# TMP.net
KiCad netlist of a schematic drawn in EAGLE
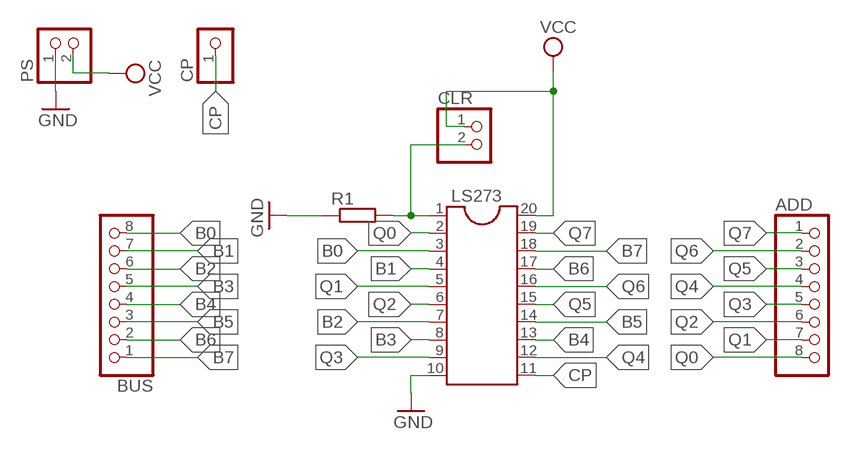
[diagram p0: schematic, sheet 1]

(export (version "E")
  (design (tool "Eeschema 10.0.6"))
  (components
    (comp (ref "ADD")
      (value "PINHD-1X8")
      (footprint "eagle-import:1X08")
      (libsource (lib "eagle-import") (part "PINHD-1X8"))
    )
    (comp (ref "BUS")
      (value "PINHD-1X8")
      (footprint "eagle-import:1X08")
      (libsource (lib "eagle-import") (part "PINHD-1X8"))
    )
    (comp (ref "CLR")
      (value "PINHD-1X2")
      (footprint "eagle-import:1X02")
      (libsource (lib "eagle-import") (part "PINHD-1X2"))
    )
    (comp (ref "CP")
      (value "PINHD-1X1")
      (footprint "eagle-import:1X01")
      (libsource (lib "eagle-import") (part "PINHD-1X1"))
    )
    (comp (ref "LS273")
      (value "DIL20S")
      (footprint "eagle-import:SOCKET-20")
      (libsource (lib "eagle-import") (part "DIL20S"))
    )
    (comp (ref "PS")
      (value "PINHD-1X2")
      (footprint "eagle-import:1X02")
      (libsource (lib "eagle-import") (part "PINHD-1X2"))
    )
    (comp (ref "R1")
      (value "R-EU_0204/7")
      (footprint "eagle-import:0204_7")
      (libsource (lib "eagle-import") (part "R-EU_0204/7"))
    )
  )
  (nets
    (net (code "1") (name "B0") (class "Default")
      (node (ref "BUS") (pin "8") (pinfunction "8_8") (pintype "passive"))
      (node (ref "LS273") (pin "3") (pinfunction "3_3") (pintype "passive"))
    )
    (net (code "2") (name "B1") (class "Default")
      (node (ref "BUS") (pin "7") (pinfunction "7_7") (pintype "passive"))
      (node (ref "LS273") (pin "4") (pinfunction "4_4") (pintype "passive"))
    )
    (net (code "3") (name "B2") (class "Default")
      (node (ref "BUS") (pin "6") (pinfunction "6_6") (pintype "passive"))
      (node (ref "LS273") (pin "7") (pinfunction "7_7") (pintype "passive"))
    )
    (net (code "4") (name "B3") (class "Default")
      (node (ref "BUS") (pin "5") (pinfunction "5_5") (pintype "passive"))
      (node (ref "LS273") (pin "8") (pinfunction "8_8") (pintype "passive"))
    )
    (net (code "5") (name "B4") (class "Default")
      (node (ref "BUS") (pin "4") (pinfunction "4_4") (pintype "passive"))
      (node (ref "LS273") (pin "13") (pinfunction "13_13") (pintype "passive"))
    )
    (net (code "6") (name "B5") (class "Default")
      (node (ref "BUS") (pin "3") (pinfunction "3_3") (pintype "passive"))
      (node (ref "LS273") (pin "14") (pinfunction "14_14") (pintype "passive"))
    )
    (net (code "7") (name "B6") (class "Default")
      (node (ref "BUS") (pin "2") (pinfunction "2_2") (pintype "passive"))
      (node (ref "LS273") (pin "17") (pinfunction "17_17") (pintype "passive"))
    )
    (net (code "8") (name "B7") (class "Default")
      (node (ref "BUS") (pin "1") (pinfunction "1_1") (pintype "passive"))
      (node (ref "LS273") (pin "18") (pinfunction "18_18") (pintype "passive"))
    )
    (net (code "9") (name "CP") (class "Default")
      (node (ref "CP") (pin "1") (pinfunction "1_1") (pintype "passive"))
      (node (ref "LS273") (pin "11") (pinfunction "11_11") (pintype "passive"))
    )
    (net (code "10") (name "GND") (class "Default")
      (node (ref "LS273") (pin "10") (pinfunction "10_10") (pintype "passive"))
      (node (ref "PS") (pin "1") (pinfunction "1_1") (pintype "passive"))
      (node (ref "R1") (pin "1") (pinfunction "1_1") (pintype "passive"))
    )
    (net (code "11") (name "Net-(CLR-Pad2)") (class "Default")
      (node (ref "CLR") (pin "2") (pinfunction "2_2") (pintype "passive"))
      (node (ref "LS273") (pin "1") (pinfunction "1_1") (pintype "passive"))
      (node (ref "R1") (pin "2") (pinfunction "2_2") (pintype "passive"))
    )
    (net (code "12") (name "Q0") (class "Default")
      (node (ref "ADD") (pin "8") (pinfunction "8_8") (pintype "passive"))
      (node (ref "LS273") (pin "2") (pinfunction "2_2") (pintype "passive"))
    )
    (net (code "13") (name "Q1") (class "Default")
      (node (ref "ADD") (pin "7") (pinfunction "7_7") (pintype "passive"))
      (node (ref "LS273") (pin "5") (pinfunction "5_5") (pintype "passive"))
    )
    (net (code "14") (name "Q2") (class "Default")
      (node (ref "ADD") (pin "6") (pinfunction "6_6") (pintype "passive"))
      (node (ref "LS273") (pin "6") (pinfunction "6_6") (pintype "passive"))
    )
    (net (code "15") (name "Q3") (class "Default")
      (node (ref "ADD") (pin "5") (pinfunction "5_5") (pintype "passive"))
      (node (ref "LS273") (pin "9") (pinfunction "9_9") (pintype "passive"))
    )
    (net (code "16") (name "Q4") (class "Default")
      (node (ref "ADD") (pin "4") (pinfunction "4_4") (pintype "passive"))
      (node (ref "LS273") (pin "12") (pinfunction "12_12") (pintype "passive"))
    )
    (net (code "17") (name "Q5") (class "Default")
      (node (ref "ADD") (pin "3") (pinfunction "3_3") (pintype "passive"))
      (node (ref "LS273") (pin "15") (pinfunction "15_15") (pintype "passive"))
    )
    (net (code "18") (name "Q6") (class "Default")
      (node (ref "ADD") (pin "2") (pinfunction "2_2") (pintype "passive"))
      (node (ref "LS273") (pin "16") (pinfunction "16_16") (pintype "passive"))
    )
    (net (code "19") (name "Q7") (class "Default")
      (node (ref "ADD") (pin "1") (pinfunction "1_1") (pintype "passive"))
      (node (ref "LS273") (pin "19") (pinfunction "19_19") (pintype "passive"))
    )
    (net (code "20") (name "VCC") (class "Default")
      (node (ref "CLR") (pin "1") (pinfunction "1_1") (pintype "passive"))
      (node (ref "LS273") (pin "20") (pinfunction "20_20") (pintype "passive"))
      (node (ref "PS") (pin "2") (pinfunction "2_2") (pintype "passive"))
    )
  )
)
